# SH6_-_CAN.net
KiCad netlist of a schematic drawn in Altium Designer
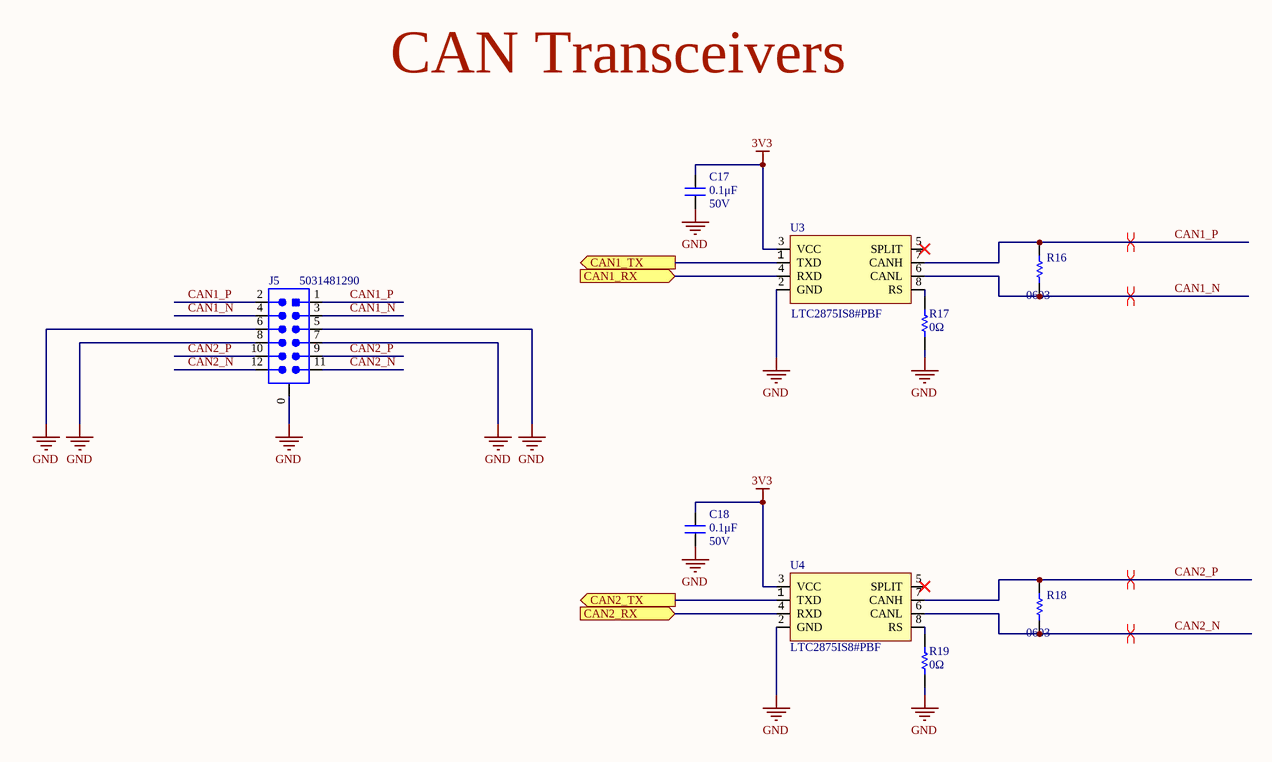
[diagram p0: SH6 - CAN.SchDoc]

(export (version "E")
  (design (tool "Eeschema 10.0.6"))
  (components
    (comp (ref "C17")
      (value "0.1μF")
      (footprint "CAP0603")
      (description "CAP CER 0.1UF 50V X7R 0603")
      (fields (field (name "VOLTAGE RATING") "50V") (field (name "Comment") "CAP_0.1uF_50V_0603"))
      (libsource (lib "UWRT_Schematic_Library_2020") (part "CAP_0.1uF_50V_0603"))
    )
    (comp (ref "C18")
      (value "0.1μF")
      (footprint "CAP0603")
      (description "CAP CER 0.1UF 50V X7R 0603")
      (fields (field (name "VOLTAGE RATING") "50V") (field (name "Comment") "CAP_0.1uF_50V_0603"))
      (libsource (lib "UWRT_Schematic_Library_2020") (part "CAP_0.1uF_50V_0603"))
    )
    (comp (ref "J5")
      (value "CON_6x2M_SM_RA")
      (footprint "MOLEX-5031481290")
      (description "CONN HEADER SMD RIGHT ANGLE 1.5MM PITCH")
      (fields (field (name "MANUFACTURER PART NUMBER 1") "5031481290"))
      (libsource (lib "UWRT_Schematic_Library_2020") (part "CON_6x2M_SM_RA"))
    )
    (comp (ref "R16")
      (value "RES_120Ω_0603_5%_HP")
      (footprint "RESC0603")
      (description "RES 120 OHM 5% 1/4W 0603")
      (fields (field (name "PACKAGE/FOOTPRINT") "0603"))
      (libsource (lib "UWRT_Schematic_Library_2020") (part "RES_120Ω_0603_5%_HP"))
    )
    (comp (ref "R17")
      (value "0Ω")
      (footprint "RESC0603")
      (description "RES 0 OHM JUMPER 1/10W 0603")
      (fields (field (name "Comment") "RES_0Ω_0603"))
      (libsource (lib "UWRT_Schematic_Library_2020") (part "RES_0Ω_0603"))
    )
    (comp (ref "R18")
      (value "RES_120Ω_0603_5%_HP")
      (footprint "RESC0603")
      (description "RES 120 OHM 5% 1/4W 0603")
      (fields (field (name "PACKAGE/FOOTPRINT") "0603"))
      (libsource (lib "UWRT_Schematic_Library_2020") (part "RES_120Ω_0603_5%_HP"))
    )
    (comp (ref "R19")
      (value "0Ω")
      (footprint "RESC0603")
      (description "RES 0 OHM JUMPER 1/10W 0603")
      (fields (field (name "Comment") "RES_0Ω_0603"))
      (libsource (lib "UWRT_Schematic_Library_2020") (part "RES_0Ω_0603"))
    )
    (comp (ref "U3")
      (value "LTC2875")
      (footprint "LT-S8_N")
      (description "IC TXRX CAN 4MBPS 8SO")
      (fields
        (field (name "MANUFACTURER PART NUMBER 1") "LTC2875IS8#PBF")
        (field (name "LCSC PART #") "C117076")
      )
      (libsource (lib "UWRT_Schematic_Library_2020") (part "LTC2875"))
    )
    (comp (ref "U4")
      (value "LTC2875")
      (footprint "LT-S8_N")
      (description "IC TXRX CAN 4MBPS 8SO")
      (fields
        (field (name "MANUFACTURER PART NUMBER 1") "LTC2875IS8#PBF")
        (field (name "LCSC PART #") "C117076")
      )
      (libsource (lib "UWRT_Schematic_Library_2020") (part "LTC2875"))
    )
  )
  (nets
    (net (code "1") (name "/CAN1_N") (class "Default")
      (node (ref "J5") (pin "3") (pinfunction "3_3") (pintype "passive"))
      (node (ref "J5") (pin "4") (pinfunction "4_4") (pintype "passive"))
      (node (ref "R16") (pin "1") (pinfunction "1_1") (pintype "passive"))
      (node (ref "U3") (pin "6") (pinfunction "CANL_6") (pintype "passive"))
    )
    (net (code "2") (name "/CAN1_P") (class "Default")
      (node (ref "J5") (pin "1") (pinfunction "1_1") (pintype "passive"))
      (node (ref "J5") (pin "2") (pinfunction "2_2") (pintype "passive"))
      (node (ref "R16") (pin "2") (pinfunction "2_2") (pintype "passive"))
      (node (ref "U3") (pin "7") (pinfunction "CANH_7") (pintype "passive"))
    )
    (net (code "3") (name "/CAN1_RX") (class "Default")
      (node (ref "U3") (pin "4") (pinfunction "RXD_4") (pintype "passive"))
    )
    (net (code "4") (name "/CAN1_TX") (class "Default")
      (node (ref "U3") (pin "1") (pinfunction "TXD_1") (pintype "passive"))
    )
    (net (code "5") (name "/CAN2_N") (class "Default")
      (node (ref "J5") (pin "11") (pinfunction "11_11") (pintype "passive"))
      (node (ref "J5") (pin "12") (pinfunction "12_12") (pintype "passive"))
      (node (ref "R18") (pin "1") (pinfunction "1_1") (pintype "passive"))
      (node (ref "U4") (pin "6") (pinfunction "CANL_6") (pintype "passive"))
    )
    (net (code "6") (name "/CAN2_P") (class "Default")
      (node (ref "J5") (pin "10") (pinfunction "10_10") (pintype "passive"))
      (node (ref "J5") (pin "9") (pinfunction "9_9") (pintype "passive"))
      (node (ref "R18") (pin "2") (pinfunction "2_2") (pintype "passive"))
      (node (ref "U4") (pin "7") (pinfunction "CANH_7") (pintype "passive"))
    )
    (net (code "7") (name "/CAN2_RX") (class "Default")
      (node (ref "U4") (pin "4") (pinfunction "RXD_4") (pintype "passive"))
    )
    (net (code "8") (name "/CAN2_TX") (class "Default")
      (node (ref "U4") (pin "1") (pinfunction "TXD_1") (pintype "passive"))
    )
    (net (code "9") (name "3V3") (class "Default")
      (node (ref "C17") (pin "1") (pinfunction "1_1") (pintype "passive"))
      (node (ref "C18") (pin "1") (pinfunction "1_1") (pintype "passive"))
      (node (ref "U3") (pin "3") (pinfunction "VCC_3") (pintype "passive"))
      (node (ref "U4") (pin "3") (pinfunction "VCC_3") (pintype "passive"))
    )
    (net (code "10") (name "GND") (class "Default")
      (node (ref "C17") (pin "2") (pinfunction "2_2") (pintype "passive"))
      (node (ref "C18") (pin "2") (pinfunction "2_2") (pintype "passive"))
      (node (ref "J5") (pin "0") (pinfunction "0_0") (pintype "passive"))
      (node (ref "J5") (pin "5") (pinfunction "5_5") (pintype "passive"))
      (node (ref "J5") (pin "6") (pinfunction "6_6") (pintype "passive"))
      (node (ref "J5") (pin "7") (pinfunction "7_7") (pintype "passive"))
      (node (ref "J5") (pin "8") (pinfunction "8_8") (pintype "passive"))
      (node (ref "R17") (pin "1") (pinfunction "1_1") (pintype "passive"))
      (node (ref "R19") (pin "1") (pinfunction "1_1") (pintype "passive"))
      (node (ref "U3") (pin "2") (pinfunction "GND_2") (pintype "passive"))
      (node (ref "U4") (pin "2") (pinfunction "GND_2") (pintype "passive"))
    )
    (net (code "11") (name "Net-(U3-RS)") (class "Default")
      (node (ref "R17") (pin "2") (pinfunction "2_2") (pintype "passive"))
      (node (ref "U3") (pin "8") (pinfunction "RS_8") (pintype "passive"))
    )
    (net (code "12") (name "Net-(U4-RS)") (class "Default")
      (node (ref "R19") (pin "2") (pinfunction "2_2") (pintype "passive"))
      (node (ref "U4") (pin "8") (pinfunction "RS_8") (pintype "passive"))
    )
    (net (code "13") (name "unconnected-(U3-SPLIT-Pad5)") (class "Default")
      (node (ref "U3") (pin "5") (pinfunction "SPLIT_5") (pintype "passive+no_connect"))
    )
    (net (code "14") (name "unconnected-(U4-SPLIT-Pad5)") (class "Default")
      (node (ref "U4") (pin "5") (pinfunction "SPLIT_5") (pintype "passive+no_connect"))
    )
  )
)
